# B503CA.net
KiCad netlist of a schematic drawn in Altium Designer
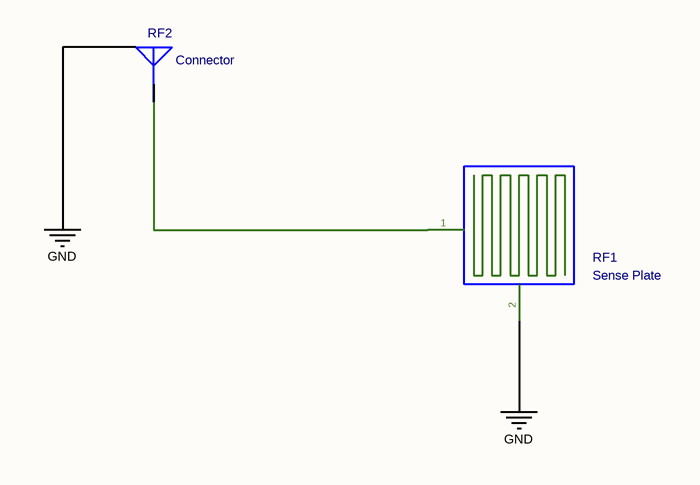
[diagram p0: B503CA.SchDoc]

(export (version "E")
  (design (tool "Eeschema 10.0.6"))
  (components
    (comp (ref "RF1")
      (value "Sense Plate")
      (footprint "Capacitve_Sense_Plate")
      (libsource (lib "Ovoo_Library") (part "PCB - Capacitive Sense Plate"))
    )
    (comp (ref "RF2")
      (value "Connector")
      (footprint "Connector_IPEX")
      (description "Analog Signal MHF4 Connector")
      (libsource (lib "Ovoo_Library") (part "Connector - MHF"))
    )
  )
  (nets
    (net (code "1") (name "GND") (class "Default")
      (node (ref "RF1") (pin "2") (pinfunction "GND_2") (pintype "power_in"))
      (node (ref "RF2") (pin "2") (pinfunction "GND_2") (pintype "passive"))
    )
    (net (code "2") (name "Net-(RF1-SIGNAL)") (class "Default")
      (node (ref "RF1") (pin "1") (pinfunction "SIGNAL_1") (pintype "passive"))
      (node (ref "RF2") (pin "1") (pinfunction "Signal_1") (pintype "passive"))
    )
  )
)
